# mk2.net
KiCad netlist of a schematic drawn in EAGLE
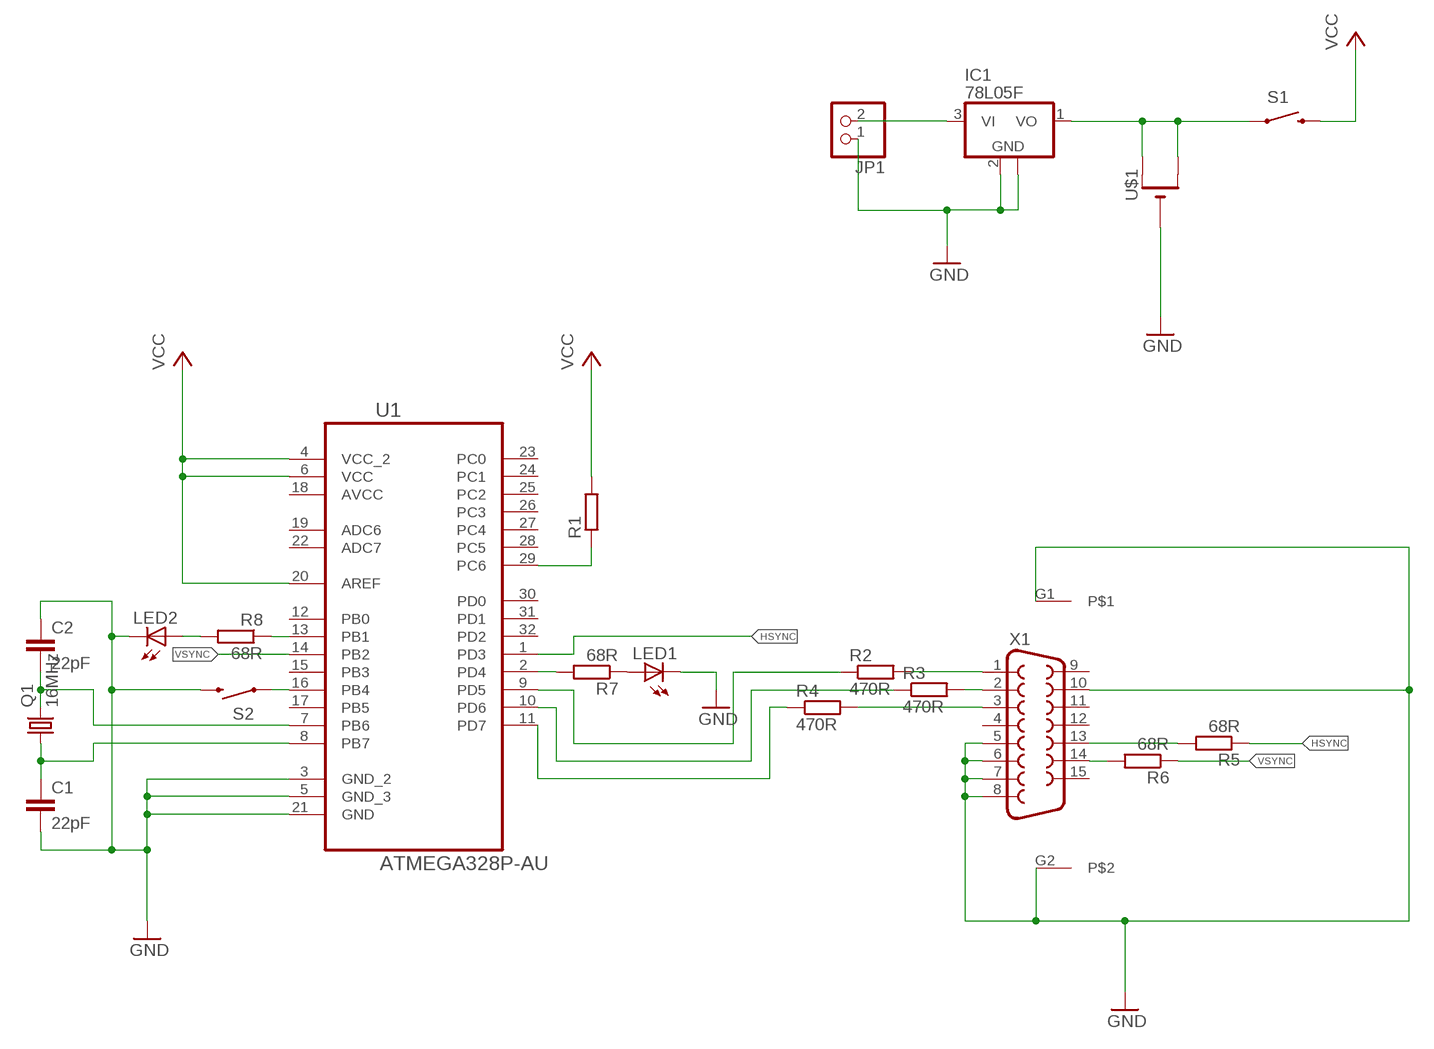
[diagram p0: schematic, sheet 1]

(export (version "E")
  (design (tool "Eeschema 10.0.6"))
  (components
    (comp (ref "C1")
      (value "22pF")
      (footprint "eagle-import:C1206")
      (libsource (lib "eagle-import") (part "C-EUC1206"))
    )
    (comp (ref "C2")
      (value "22pF")
      (footprint "eagle-import:C1206")
      (libsource (lib "eagle-import") (part "C-EUC1206"))
    )
    (comp (ref "IC1")
      (value "78L05F")
      (footprint "eagle-import:SOT89")
      (libsource (lib "eagle-import") (part "78LF05"))
    )
    (comp (ref "JP1")
      (value "PINHD-1X2")
      (footprint "eagle-import:1X02")
      (libsource (lib "eagle-import") (part "PINHD-1X2"))
    )
    (comp (ref "LED1")
      (value "LEDCHIPLED_1206")
      (footprint "eagle-import:CHIPLED_1206")
      (libsource (lib "eagle-import") (part "LEDCHIPLED_1206"))
    )
    (comp (ref "LED2")
      (value "LEDCHIPLED_1206")
      (footprint "eagle-import:CHIPLED_1206")
      (libsource (lib "eagle-import") (part "LEDCHIPLED_1206"))
    )
    (comp (ref "Q1")
      (value "16MHz")
      (footprint "eagle-import:HC49UP")
      (libsource (lib "eagle-import") (part "CRYSTALHC49UP"))
    )
    (comp (ref "R1")
      (value "R-EU_M1206")
      (footprint "eagle-import:M1206")
      (libsource (lib "eagle-import") (part "R-EU_M1206"))
    )
    (comp (ref "R2")
      (value "470R")
      (footprint "eagle-import:M1206")
      (libsource (lib "eagle-import") (part "R-EU_M1206"))
    )
    (comp (ref "R3")
      (value "470R")
      (footprint "eagle-import:M1206")
      (libsource (lib "eagle-import") (part "R-EU_M1206"))
    )
    (comp (ref "R4")
      (value "470R")
      (footprint "eagle-import:M1206")
      (libsource (lib "eagle-import") (part "R-EU_M1206"))
    )
    (comp (ref "R5")
      (value "68R")
      (footprint "eagle-import:M1206")
      (libsource (lib "eagle-import") (part "R-EU_M1206"))
    )
    (comp (ref "R6")
      (value "68R")
      (footprint "eagle-import:M1206")
      (libsource (lib "eagle-import") (part "R-EU_M1206"))
    )
    (comp (ref "R7")
      (value "68R")
      (footprint "eagle-import:M1206")
      (libsource (lib "eagle-import") (part "R-EU_M1206"))
    )
    (comp (ref "R8")
      (value "68R")
      (footprint "eagle-import:M1206")
      (libsource (lib "eagle-import") (part "R-EU_M1206"))
    )
    (comp (ref "S1")
      (value "SWITCH-MOMENTARY-2TACTILE-SWITCH-SMD-RIGHT-ANGLE")
      (footprint "eagle-import:TACTILE_SWITCH-SMD-RIGHT-ANGLE")
      (libsource (lib "eagle-import") (part "SWITCH-MOMENTARY-2TACTILE-SWITCH-SMD-RIGHT-ANGLE"))
    )
    (comp (ref "S2")
      (value "SWITCH-MOMENTARY-2TACTILE-SWITCH-SMD-RIGHT-ANGLE")
      (footprint "eagle-import:TACTILE_SWITCH-SMD-RIGHT-ANGLE")
      (libsource (lib "eagle-import") (part "SWITCH-MOMENTARY-2TACTILE-SWITCH-SMD-RIGHT-ANGLE"))
    )
    (comp (ref "U$1")
      (value "CR2032SMT")
      (footprint "eagle-import:CR2032-SMD")
      (libsource (lib "eagle-import") (part "CR2032SMT"))
    )
    (comp (ref "U1")
      (value "ATMEGA328P-AU")
      (footprint "eagle-import:QFP80P900X900X120-32N")
      (libsource (lib "eagle-import") (part "ATMEGA328P-AU"))
    )
    (comp (ref "X1")
      (value "F15HDV")
      (footprint "eagle-import:HDF15V")
      (libsource (lib "eagle-import") (part "F15HDV"))
    )
  )
  (nets
    (net (code "1") (name "/AVCC") (class "Default")
      (node (ref "U1") (pin "18") (pinfunction "AVCC_18") (pintype "power_in"))
    )
    (net (code "2") (name "GND") (class "Default")
      (node (ref "C1") (pin "2") (pinfunction "2_2") (pintype "passive"))
      (node (ref "C2") (pin "1") (pinfunction "1_1") (pintype "passive"))
      (node (ref "IC1") (pin "2") (pinfunction "GND_2") (pintype "passive"))
      (node (ref "IC1") (pin "2@1") (pinfunction "GND_2@1") (pintype "passive"))
      (node (ref "JP1") (pin "1") (pinfunction "1_1") (pintype "passive"))
      (node (ref "LED1") (pin "C") (pinfunction "C_C") (pintype "passive"))
      (node (ref "LED2") (pin "C") (pinfunction "C_C") (pintype "passive"))
      (node (ref "S2") (pin "2") (pinfunction "2_2") (pintype "passive"))
      (node (ref "U$1") (pin "-") (pinfunction "-_-") (pintype "passive"))
      (node (ref "U1") (pin "21") (pinfunction "GND_21") (pintype "passive"))
      (node (ref "U1") (pin "3") (pinfunction "GND_2_3") (pintype "passive"))
      (node (ref "U1") (pin "5") (pinfunction "GND_3_5") (pintype "passive"))
      (node (ref "X1") (pin "10") (pinfunction "10_10") (pintype "passive"))
      (node (ref "X1") (pin "5") (pinfunction "5_5") (pintype "passive"))
      (node (ref "X1") (pin "6") (pinfunction "6_6") (pintype "passive"))
      (node (ref "X1") (pin "7") (pinfunction "7_7") (pintype "passive"))
      (node (ref "X1") (pin "8") (pinfunction "8_8") (pintype "passive"))
      (node (ref "X1") (pin "G1") (pinfunction "P$1_G1") (pintype "bidirectional"))
      (node (ref "X1") (pin "G2") (pinfunction "P$2_G2") (pintype "bidirectional"))
    )
    (net (code "3") (name "HSYNC") (class "Default")
      (node (ref "R5") (pin "1") (pinfunction "1_1") (pintype "passive"))
      (node (ref "U1") (pin "1") (pinfunction "PD3_1") (pintype "bidirectional"))
    )
    (net (code "4") (name "Net-(IC1-VI)") (class "Default")
      (node (ref "IC1") (pin "3") (pinfunction "VI_3") (pintype "input"))
      (node (ref "JP1") (pin "2") (pinfunction "2_2") (pintype "passive"))
    )
    (net (code "5") (name "Net-(IC1-VO)") (class "Default")
      (node (ref "IC1") (pin "1") (pinfunction "VO_1") (pintype "passive"))
      (node (ref "S1") (pin "1") (pinfunction "1_1") (pintype "passive"))
      (node (ref "U$1") (pin "+$1") (pinfunction "+_+$1") (pintype "passive"))
      (node (ref "U$1") (pin "+$2") (pinfunction "+1_+$2") (pintype "passive"))
    )
    (net (code "6") (name "Net-(LED1-PadA)") (class "Default")
      (node (ref "LED1") (pin "A") (pinfunction "A_A") (pintype "passive"))
      (node (ref "R7") (pin "1") (pinfunction "1_1") (pintype "passive"))
    )
    (net (code "7") (name "Net-(LED2-PadA)") (class "Default")
      (node (ref "LED2") (pin "A") (pinfunction "A_A") (pintype "passive"))
      (node (ref "R8") (pin "2") (pinfunction "2_2") (pintype "passive"))
    )
    (net (code "8") (name "Net-(R2-Pad2)") (class "Default")
      (node (ref "R2") (pin "2") (pinfunction "2_2") (pintype "passive"))
      (node (ref "X1") (pin "1") (pinfunction "1_1") (pintype "passive"))
    )
    (net (code "9") (name "Net-(R3-Pad2)") (class "Default")
      (node (ref "R3") (pin "2") (pinfunction "2_2") (pintype "passive"))
      (node (ref "X1") (pin "2") (pinfunction "2_2") (pintype "passive"))
    )
    (net (code "10") (name "Net-(R4-Pad2)") (class "Default")
      (node (ref "R4") (pin "2") (pinfunction "2_2") (pintype "passive"))
      (node (ref "X1") (pin "3") (pinfunction "3_3") (pintype "passive"))
    )
    (net (code "11") (name "Net-(R5-Pad2)") (class "Default")
      (node (ref "R5") (pin "2") (pinfunction "2_2") (pintype "passive"))
      (node (ref "X1") (pin "13") (pinfunction "13_13") (pintype "passive"))
    )
    (net (code "12") (name "Net-(R6-Pad2)") (class "Default")
      (node (ref "R6") (pin "2") (pinfunction "2_2") (pintype "passive"))
      (node (ref "X1") (pin "14") (pinfunction "14_14") (pintype "passive"))
    )
    (net (code "13") (name "Net-(U1-PB1)") (class "Default")
      (node (ref "R8") (pin "1") (pinfunction "1_1") (pintype "passive"))
      (node (ref "U1") (pin "13") (pinfunction "PB1_13") (pintype "bidirectional"))
    )
    (net (code "14") (name "Net-(U1-PB4)") (class "Default")
      (node (ref "S2") (pin "1") (pinfunction "1_1") (pintype "passive"))
      (node (ref "U1") (pin "16") (pinfunction "PB4_16") (pintype "bidirectional"))
    )
    (net (code "15") (name "Net-(U1-PB6)") (class "Default")
      (node (ref "C2") (pin "2") (pinfunction "2_2") (pintype "passive"))
      (node (ref "Q1") (pin "2") (pinfunction "2_2") (pintype "passive"))
      (node (ref "U1") (pin "7") (pinfunction "PB6_7") (pintype "bidirectional"))
    )
    (net (code "16") (name "Net-(U1-PB7)") (class "Default")
      (node (ref "C1") (pin "1") (pinfunction "1_1") (pintype "passive"))
      (node (ref "Q1") (pin "1") (pinfunction "1_1") (pintype "passive"))
      (node (ref "U1") (pin "8") (pinfunction "PB7_8") (pintype "bidirectional"))
    )
    (net (code "17") (name "Net-(U1-PC6)") (class "Default")
      (node (ref "R1") (pin "1") (pinfunction "1_1") (pintype "passive"))
      (node (ref "U1") (pin "29") (pinfunction "PC6_29") (pintype "bidirectional"))
    )
    (net (code "18") (name "Net-(U1-PD4)") (class "Default")
      (node (ref "R7") (pin "2") (pinfunction "2_2") (pintype "passive"))
      (node (ref "U1") (pin "2") (pinfunction "PD4_2") (pintype "bidirectional"))
    )
    (net (code "19") (name "Net-(U1-PD5)") (class "Default")
      (node (ref "R2") (pin "1") (pinfunction "1_1") (pintype "passive"))
      (node (ref "U1") (pin "9") (pinfunction "PD5_9") (pintype "bidirectional"))
    )
    (net (code "20") (name "Net-(U1-PD6)") (class "Default")
      (node (ref "R3") (pin "1") (pinfunction "1_1") (pintype "passive"))
      (node (ref "U1") (pin "10") (pinfunction "PD6_10") (pintype "bidirectional"))
    )
    (net (code "21") (name "Net-(U1-PD7)") (class "Default")
      (node (ref "R4") (pin "1") (pinfunction "1_1") (pintype "passive"))
      (node (ref "U1") (pin "11") (pinfunction "PD7_11") (pintype "bidirectional"))
    )
    (net (code "22") (name "VCC") (class "Default")
      (node (ref "R1") (pin "2") (pinfunction "2_2") (pintype "passive"))
      (node (ref "S1") (pin "2") (pinfunction "2_2") (pintype "passive"))
      (node (ref "U1") (pin "20") (pinfunction "AREF_20") (pintype "input"))
      (node (ref "U1") (pin "4") (pinfunction "VCC_2_4") (pintype "power_in"))
      (node (ref "U1") (pin "6") (pinfunction "VCC_6") (pintype "power_in"))
    )
    (net (code "23") (name "VSYNC") (class "Default")
      (node (ref "R6") (pin "1") (pinfunction "1_1") (pintype "passive"))
      (node (ref "U1") (pin "14") (pinfunction "PB2_14") (pintype "bidirectional"))
    )
    (net (code "24") (name "unconnected-(U1-ADC6-Pad19)") (class "Default")
      (node (ref "U1") (pin "19") (pinfunction "ADC6_19") (pintype "input"))
    )
    (net (code "25") (name "unconnected-(U1-ADC7-Pad22)") (class "Default")
      (node (ref "U1") (pin "22") (pinfunction "ADC7_22") (pintype "input"))
    )
    (net (code "26") (name "unconnected-(U1-PB0-Pad12)") (class "Default")
      (node (ref "U1") (pin "12") (pinfunction "PB0_12") (pintype "bidirectional"))
    )
    (net (code "27") (name "unconnected-(U1-PB3-Pad15)") (class "Default")
      (node (ref "U1") (pin "15") (pinfunction "PB3_15") (pintype "bidirectional"))
    )
    (net (code "28") (name "unconnected-(U1-PB5-Pad17)") (class "Default")
      (node (ref "U1") (pin "17") (pinfunction "PB5_17") (pintype "bidirectional"))
    )
    (net (code "29") (name "unconnected-(U1-PC0-Pad23)") (class "Default")
      (node (ref "U1") (pin "23") (pinfunction "PC0_23") (pintype "bidirectional"))
    )
    (net (code "30") (name "unconnected-(U1-PC1-Pad24)") (class "Default")
      (node (ref "U1") (pin "24") (pinfunction "PC1_24") (pintype "bidirectional"))
    )
    (net (code "31") (name "unconnected-(U1-PC2-Pad25)") (class "Default")
      (node (ref "U1") (pin "25") (pinfunction "PC2_25") (pintype "bidirectional"))
    )
    (net (code "32") (name "unconnected-(U1-PC3-Pad26)") (class "Default")
      (node (ref "U1") (pin "26") (pinfunction "PC3_26") (pintype "bidirectional"))
    )
    (net (code "33") (name "unconnected-(U1-PC4-Pad27)") (class "Default")
      (node (ref "U1") (pin "27") (pinfunction "PC4_27") (pintype "bidirectional"))
    )
    (net (code "34") (name "unconnected-(U1-PC5-Pad28)") (class "Default")
      (node (ref "U1") (pin "28") (pinfunction "PC5_28") (pintype "bidirectional"))
    )
    (net (code "35") (name "unconnected-(U1-PD0-Pad30)") (class "Default")
      (node (ref "U1") (pin "30") (pinfunction "PD0_30") (pintype "bidirectional"))
    )
    (net (code "36") (name "unconnected-(U1-PD1-Pad31)") (class "Default")
      (node (ref "U1") (pin "31") (pinfunction "PD1_31") (pintype "bidirectional"))
    )
    (net (code "37") (name "unconnected-(U1-PD2-Pad32)") (class "Default")
      (node (ref "U1") (pin "32") (pinfunction "PD2_32") (pintype "bidirectional"))
    )
    (net (code "38") (name "unconnected-(X1-Pad4)") (class "Default")
      (node (ref "X1") (pin "4") (pinfunction "4_4") (pintype "passive"))
    )
    (net (code "39") (name "unconnected-(X1-Pad9)") (class "Default")
      (node (ref "X1") (pin "9") (pinfunction "9_9") (pintype "passive"))
    )
    (net (code "40") (name "unconnected-(X1-Pad11)") (class "Default")
      (node (ref "X1") (pin "11") (pinfunction "11_11") (pintype "passive"))
    )
    (net (code "41") (name "unconnected-(X1-Pad12)") (class "Default")
      (node (ref "X1") (pin "12") (pinfunction "12_12") (pintype "passive"))
    )
    (net (code "42") (name "unconnected-(X1-Pad15)") (class "Default")
      (node (ref "X1") (pin "15") (pinfunction "15_15") (pintype "passive"))
    )
  )
)
